# Motor_Driver_2.net
KiCad netlist of a schematic drawn in Altium Designer
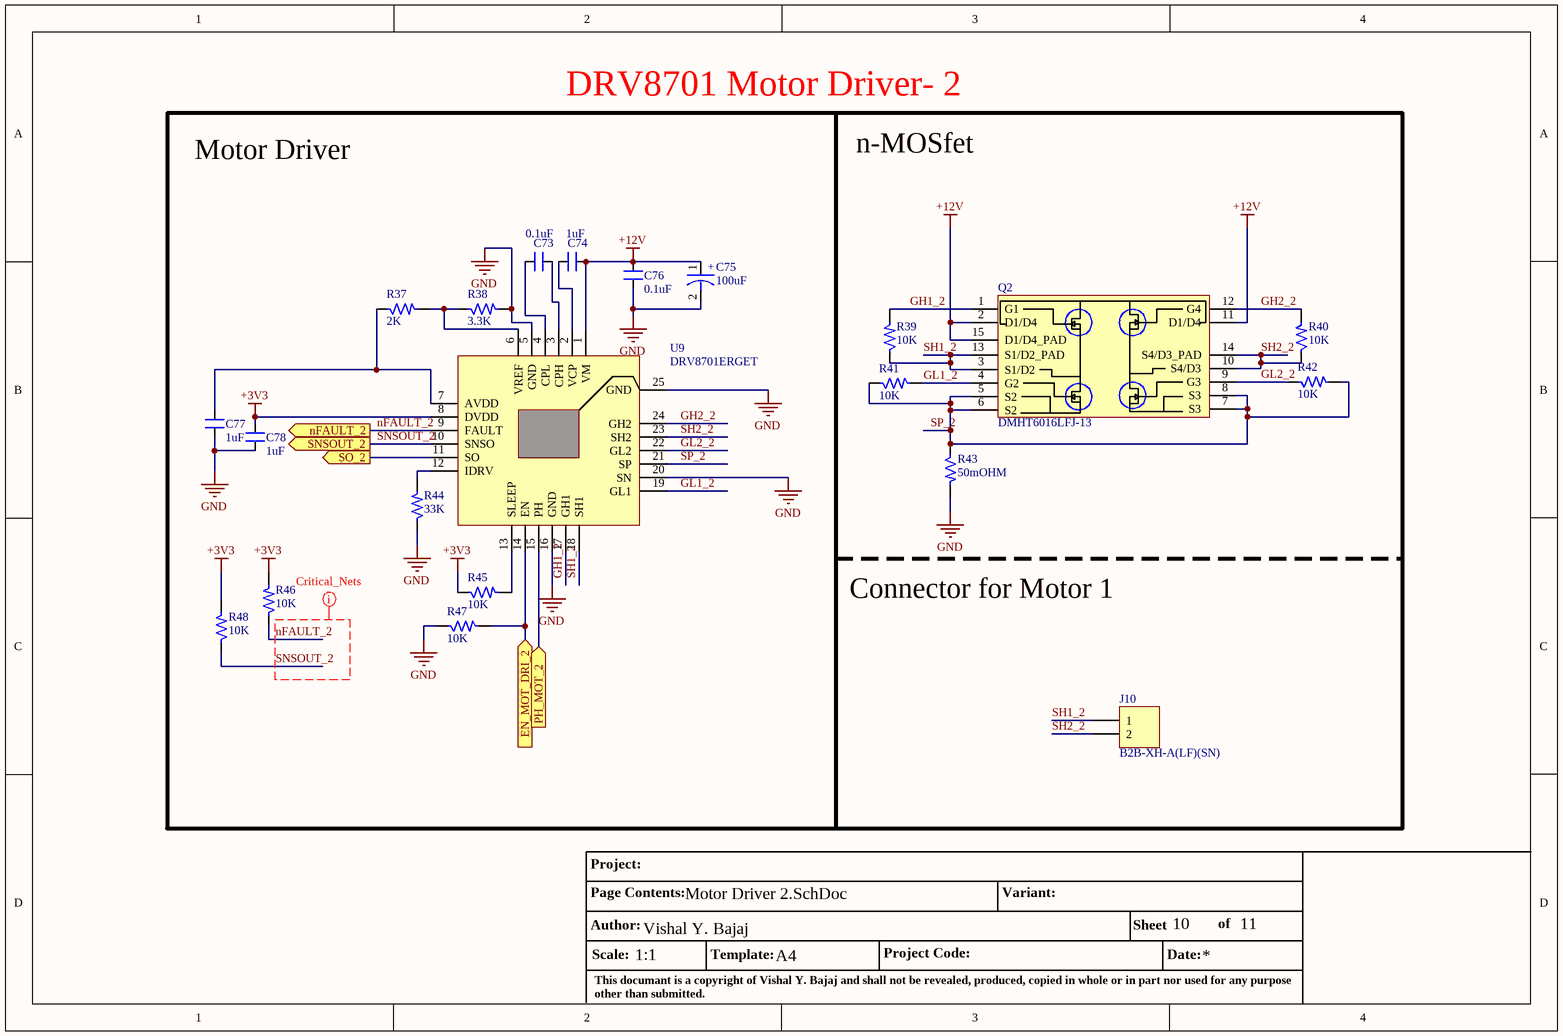
[diagram p0: Motor Driver 2.SchDoc]

(export (version "E")
  (design (tool "Eeschema 10.0.6"))
  (components
    (comp (ref "C73")
      (value "0.1uF")
      (footprint "CAP_0805")
      (description "0.1µF ±10% 50V Ceramic Capacitor X7R 0805 (2012 Metric)")
      (fields
        (field (name "MANUFACTURER") "Samsung")
        (field (name "MANUFACTURER PART NUMBER") "CL21B104KBCNNNC")
      )
      (libsource (lib "ESTEEMPCBLIB") (part "CAP_0.1uF-50V-10%-0805"))
    )
    (comp (ref "C74")
      (value "1uF")
      (footprint "CAP_0805")
      (description "1µF ±5% 50V Ceramic Capacitor X7R 0805 (2012 Metric)")
      (fields
        (field (name "MANUFACTURER") "Samsung")
        (field (name "MANUFACTURER PART NUMBER") "CC0805JKX7R9BB105")
      )
      (libsource (lib "ESTEEMPCBLIB") (part "CAP_1uF-50V-5%-0805"))
    )
    (comp (ref "C75")
      (value "100uF")
      (footprint "ACAP_P236_D305_H303_RAD")
      (description "100µF 25V Aluminum Electrolytic Capacitors Radial, Can - SMD 1000 Hrs @ 105°C")
      (fields
        (field (name "MANUFACTURER") "Nichicon")
        (field (name "MANUFACTURER PART NUMBER") "UWT1E101MCL1GS")
      )
      (libsource (lib "ESTEEMPCBLIB") (part "CAP-P_100uF-25V-20%-RAD"))
    )
    (comp (ref "C76")
      (value "0.1uF")
      (footprint "CAP_0805")
      (description "0.1µF ±10% 50V Ceramic Capacitor X7R 0805 (2012 Metric)")
      (fields
        (field (name "MANUFACTURER") "Samsung")
        (field (name "MANUFACTURER PART NUMBER") "CL21B104KBCNNNC")
      )
      (libsource (lib "ESTEEMPCBLIB") (part "CAP_0.1uF-50V-10%-0805"))
    )
    (comp (ref "C77")
      (value "1uF")
      (footprint "CAP_0805")
      (description "1µF ±5% 50V Ceramic Capacitor X7R 0805 (2012 Metric)")
      (fields
        (field (name "MANUFACTURER") "Samsung")
        (field (name "MANUFACTURER PART NUMBER") "CC0805JKX7R9BB105")
      )
      (libsource (lib "ESTEEMPCBLIB") (part "CAP_1uF-50V-5%-0805"))
    )
    (comp (ref "C78")
      (value "1uF")
      (footprint "CAP_0805")
      (description "1µF ±5% 50V Ceramic Capacitor X7R 0805 (2012 Metric)")
      (fields
        (field (name "MANUFACTURER") "Samsung")
        (field (name "MANUFACTURER PART NUMBER") "CC0805JKX7R9BB105")
      )
      (libsource (lib "ESTEEMPCBLIB") (part "CAP_1uF-50V-5%-0805"))
    )
    (comp (ref "J10")
      (value "B2B-XH-A(LF)(SN)")
      (footprint "CON2_100_B2B-XH-A_TH_ST")
      (description "2 Pins, 1 Row 2.54mm Pitch, Straight Connector, male")
      (fields (field (name "MANUFACTURER") "JST") (field (name "MATING PART NUMBER") "XHP-2"))
      (libsource (lib "ESTEEMPCBLIB") (part "CON-PLG_2X1-100-ST-TH"))
    )
    (comp (ref "Q2")
      (value "DMHT6016LFJ-13")
      (footprint "DFN5045-12_33_212_27X15_SMD_1")
      (description "Mosfet Array 4 N-Channel 14.8A (Ta) Surface Mount V-DFN5045-12")
      (fields (field (name "MANUFACTURER") "ON Semiconductor"))
      (libsource (lib "ESTEEMPCBLIB") (part "MOSFET-N_60V-14.8A-V-DFN5045-12"))
    )
    (comp (ref "R37")
      (value "2K")
      (footprint "RES_0805")
      (description "2 kOhms ±1% 0.125W, 1/8W Chip Resistor 0805 (2012 Metric) Moisture Resistant Thick Film")
      (fields
        (field (name "MANUFACTURER") "TE Connectivity")
        (field (name "MANUFACTURER PART NUMBER") "RC0805FR-072KL")
      )
      (libsource (lib "ESTEEMPCBLIB") (part "RES_2K-0.125W-1%-0805"))
    )
    (comp (ref "R38")
      (value "3.3K")
      (footprint "RES_0805")
      (description "3.3 kOhms ±1% 0.125W, 1/8W Chip Resistor 0805 (2012 Metric) Thick Film")
      (fields (field (name "MANUFACTURER") "Panasonic") (field (name "MANUFACTURER PART NUMBER") "1623214-1"))
      (libsource (lib "ESTEEMPCBLIB") (part "RES_3.3K-0.125W-1%-0805"))
    )
    (comp (ref "R39")
      (value "10K")
      (footprint "RES_0603")
      (description "10 kOhms ±1% 0.1W, 1/10W Chip Resistor 0603 (1608 Metric) Automotive AEC-Q200 Thick Film")
      (fields (field (name "MANUFACTURER") "Walsin") (field (name "MANUFACTURER PART NUMBER") "WR06X1002FTL"))
      (libsource (lib "ESTEEMPCBLIB") (part "RES_10K-0.1W-1%-0603"))
    )
    (comp (ref "R40")
      (value "10K")
      (footprint "RES_0603")
      (description "10 kOhms ±1% 0.1W, 1/10W Chip Resistor 0603 (1608 Metric) Automotive AEC-Q200 Thick Film")
      (fields (field (name "MANUFACTURER") "Walsin") (field (name "MANUFACTURER PART NUMBER") "WR06X1002FTL"))
      (libsource (lib "ESTEEMPCBLIB") (part "RES_10K-0.1W-1%-0603"))
    )
    (comp (ref "R41")
      (value "10K")
      (footprint "RES_0603")
      (description "10 kOhms ±1% 0.1W, 1/10W Chip Resistor 0603 (1608 Metric) Automotive AEC-Q200 Thick Film")
      (fields (field (name "MANUFACTURER") "Walsin") (field (name "MANUFACTURER PART NUMBER") "WR06X1002FTL"))
      (libsource (lib "ESTEEMPCBLIB") (part "RES_10K-0.1W-1%-0603"))
    )
    (comp (ref "R42")
      (value "10K")
      (footprint "RES_0603")
      (description "10 kOhms ±1% 0.1W, 1/10W Chip Resistor 0603 (1608 Metric) Automotive AEC-Q200 Thick Film")
      (fields (field (name "MANUFACTURER") "Walsin") (field (name "MANUFACTURER PART NUMBER") "WR06X1002FTL"))
      (libsource (lib "ESTEEMPCBLIB") (part "RES_10K-0.1W-1%-0603"))
    )
    (comp (ref "R43")
      (value "50mOHM")
      (footprint "RES_2512")
      (fields
        (field (name "MANUFACTURER") "Yageo")
        (field (name "MANUFACTURER PART NUMBER") "PA2512FKF7W0R05E")
      )
      (libsource (lib "ESTEEMPCBLIB") (part "RES_50mOhm-2W-1%-2512"))
    )
    (comp (ref "R44")
      (value "33K")
      (footprint "RES_0805")
      (fields
        (field (name "MANUFACTURER") "Vishay BCcomponents")
        (field (name "MANUFACTURER PART NUMBER") "CRG0805F33K")
      )
      (libsource (lib "ESTEEMPCBLIB") (part "RES_33K-0.125W-1%-0805"))
    )
    (comp (ref "R45")
      (value "10K")
      (footprint "RES_0603")
      (description "10 kOhms ±1% 0.1W, 1/10W Chip Resistor 0603 (1608 Metric) Automotive AEC-Q200 Thick Film")
      (fields (field (name "MANUFACTURER") "Walsin") (field (name "MANUFACTURER PART NUMBER") "WR06X1002FTL"))
      (libsource (lib "ESTEEMPCBLIB") (part "RES_10K-0.1W-1%-0603"))
    )
    (comp (ref "R46")
      (value "10K")
      (footprint "RES_0805")
      (description "10 kOhms ±1% 0.125W, 1/8W Chip Resistor 0805 (2012 Metric) Automotive AEC-Q200 Thick Film")
      (fields (field (name "MANUFACTURER") "CTS") (field (name "MANUFACTURER PART NUMBER") "WR08X1002FTL"))
      (libsource (lib "ESTEEMPCBLIB") (part "RES_10K-0.125W-1%-0805"))
    )
    (comp (ref "R47")
      (value "10K")
      (footprint "RES_0603")
      (description "10 kOhms ±1% 0.1W, 1/10W Chip Resistor 0603 (1608 Metric) Automotive AEC-Q200 Thick Film")
      (fields (field (name "MANUFACTURER") "Walsin") (field (name "MANUFACTURER PART NUMBER") "WR06X1002FTL"))
      (libsource (lib "ESTEEMPCBLIB") (part "RES_10K-0.1W-1%-0603"))
    )
    (comp (ref "R48")
      (value "10K")
      (footprint "RES_0805")
      (description "10 kOhms ±1% 0.125W, 1/8W Chip Resistor 0805 (2012 Metric) Automotive AEC-Q200 Thick Film")
      (fields (field (name "MANUFACTURER") "CTS") (field (name "MANUFACTURER PART NUMBER") "WR08X1002FTL"))
      (libsource (lib "ESTEEMPCBLIB") (part "RES_10K-0.125W-1%-0805"))
    )
    (comp (ref "U9")
      (value "DRV8701ERGET")
      (footprint "VFQFN24_19.6_196_12X32_SMD_1")
      (description "Motor Driver Power MOSFET Parallel 24-VQFN (4x4)")
      (fields (field (name "MANUFACTURER") "Texas Instruments"))
      (libsource (lib "ESTEEMPCBLIB") (part "IC_DRV8701ERGET"))
    )
  )
  (nets
    (net (code "1") (name "+3V3") (class "Default")
      (node (ref "C78") (pin "2") (pinfunction "2_2") (pintype "passive"))
      (node (ref "R45") (pin "1") (pinfunction "1_1") (pintype "passive"))
      (node (ref "R46") (pin "2") (pinfunction "2_2") (pintype "passive"))
      (node (ref "R48") (pin "2") (pinfunction "2_2") (pintype "passive"))
      (node (ref "U9") (pin "8") (pinfunction "DVDD_8") (pintype "passive"))
    )
    (net (code "2") (name "+12V") (class "Default")
      (node (ref "C74") (pin "2") (pinfunction "2_2") (pintype "passive"))
      (node (ref "C75") (pin "1") (pinfunction "1_1") (pintype "passive"))
      (node (ref "C76") (pin "2") (pinfunction "2_2") (pintype "passive"))
      (node (ref "Q2") (pin "11") (pinfunction "D1/D4_11") (pintype "passive"))
      (node (ref "Q2") (pin "15") (pinfunction "D1/D4_PAD_15") (pintype "passive"))
      (node (ref "Q2") (pin "2") (pinfunction "D1/D4_2") (pintype "passive"))
      (node (ref "U9") (pin "1") (pinfunction "VM_1") (pintype "passive"))
    )
    (net (code "3") (name "/EN_MOT_DRI_2") (class "Default")
      (node (ref "R47") (pin "2") (pinfunction "2_2") (pintype "passive"))
      (node (ref "U9") (pin "14") (pinfunction "EN_14") (pintype "passive"))
    )
    (net (code "4") (name "/GH1_2") (class "Default")
      (node (ref "Q2") (pin "1") (pinfunction "G1_1") (pintype "passive"))
      (node (ref "R39") (pin "2") (pinfunction "2_2") (pintype "passive"))
      (node (ref "U9") (pin "17") (pinfunction "GH1_17") (pintype "passive"))
    )
    (net (code "5") (name "/GH2_2") (class "Default")
      (node (ref "Q2") (pin "12") (pinfunction "G4_12") (pintype "passive"))
      (node (ref "R40") (pin "2") (pinfunction "2_2") (pintype "passive"))
      (node (ref "U9") (pin "24") (pinfunction "GH2_24") (pintype "passive"))
    )
    (net (code "6") (name "/GL1_2") (class "Default")
      (node (ref "Q2") (pin "4") (pinfunction "G2_4") (pintype "passive"))
      (node (ref "R41") (pin "2") (pinfunction "2_2") (pintype "passive"))
      (node (ref "U9") (pin "19") (pinfunction "GL1_19") (pintype "passive"))
    )
    (net (code "7") (name "/GL2_2") (class "Default")
      (node (ref "Q2") (pin "9") (pinfunction "G3_9") (pintype "passive"))
      (node (ref "R42") (pin "1") (pinfunction "1_1") (pintype "passive"))
      (node (ref "U9") (pin "22") (pinfunction "GL2_22") (pintype "passive"))
    )
    (net (code "8") (name "/PH_MOT_2") (class "Default")
      (node (ref "U9") (pin "15") (pinfunction "PH_15") (pintype "passive"))
    )
    (net (code "9") (name "/SH1_2") (class "Default")
      (node (ref "J10") (pin "1") (pinfunction "1_1") (pintype "passive"))
      (node (ref "Q2") (pin "13") (pinfunction "S1/D2_PAD_13") (pintype "passive"))
      (node (ref "Q2") (pin "3") (pinfunction "S1/D2_3") (pintype "passive"))
      (node (ref "R39") (pin "1") (pinfunction "1_1") (pintype "passive"))
      (node (ref "U9") (pin "18") (pinfunction "SH1_18") (pintype "passive"))
    )
    (net (code "10") (name "/SH2_2") (class "Default")
      (node (ref "J10") (pin "2") (pinfunction "2_2") (pintype "passive"))
      (node (ref "Q2") (pin "10") (pinfunction "S4/D3_10") (pintype "passive"))
      (node (ref "Q2") (pin "14") (pinfunction "S4/D3_PAD_14") (pintype "passive"))
      (node (ref "R40") (pin "1") (pinfunction "1_1") (pintype "passive"))
      (node (ref "U9") (pin "23") (pinfunction "SH2_23") (pintype "passive"))
    )
    (net (code "11") (name "/SNSOUT_2") (class "Default")
      (node (ref "R48") (pin "1") (pinfunction "1_1") (pintype "passive"))
      (node (ref "U9") (pin "10") (pinfunction "SNSO_10") (pintype "passive"))
    )
    (net (code "12") (name "/SO_2") (class "Default")
      (node (ref "U9") (pin "11") (pinfunction "SO_11") (pintype "passive"))
    )
    (net (code "13") (name "/SP_2") (class "Default")
      (node (ref "Q2") (pin "5") (pinfunction "S2_5") (pintype "passive"))
      (node (ref "Q2") (pin "6") (pinfunction "S2_6") (pintype "passive"))
      (node (ref "Q2") (pin "7") (pinfunction "S3_7") (pintype "passive"))
      (node (ref "Q2") (pin "8") (pinfunction "S3_8") (pintype "passive"))
      (node (ref "R41") (pin "1") (pinfunction "1_1") (pintype "passive"))
      (node (ref "R42") (pin "2") (pinfunction "2_2") (pintype "passive"))
      (node (ref "R43") (pin "1") (pinfunction "1_1") (pintype "passive"))
      (node (ref "U9") (pin "21") (pinfunction "SP_21") (pintype "passive"))
    )
    (net (code "14") (name "/nFAULT_2") (class "Default")
      (node (ref "R46") (pin "1") (pinfunction "1_1") (pintype "passive"))
      (node (ref "U9") (pin "9") (pinfunction "FAULT_9") (pintype "passive"))
    )
    (net (code "15") (name "GND") (class "Default")
      (node (ref "C75") (pin "2") (pinfunction "2_2") (pintype "passive"))
      (node (ref "C76") (pin "1") (pinfunction "1_1") (pintype "passive"))
      (node (ref "C77") (pin "1") (pinfunction "1_1") (pintype "passive"))
      (node (ref "C78") (pin "1") (pinfunction "1_1") (pintype "passive"))
      (node (ref "R38") (pin "2") (pinfunction "2_2") (pintype "passive"))
      (node (ref "R43") (pin "2") (pinfunction "2_2") (pintype "passive"))
      (node (ref "R44") (pin "1") (pinfunction "1_1") (pintype "passive"))
      (node (ref "R47") (pin "1") (pinfunction "1_1") (pintype "passive"))
      (node (ref "U9") (pin "16") (pinfunction "GND_16") (pintype "passive"))
      (node (ref "U9") (pin "20") (pinfunction "SN_20") (pintype "passive"))
      (node (ref "U9") (pin "25") (pinfunction "GND_25") (pintype "passive"))
      (node (ref "U9") (pin "5") (pinfunction "GND_5") (pintype "passive"))
    )
    (net (code "16") (name "Net-(U9-AVDD)") (class "Default")
      (node (ref "C77") (pin "2") (pinfunction "2_2") (pintype "passive"))
      (node (ref "R37") (pin "1") (pinfunction "1_1") (pintype "passive"))
      (node (ref "U9") (pin "7") (pinfunction "AVDD_7") (pintype "passive"))
    )
    (net (code "17") (name "Net-(U9-CPH)") (class "Default")
      (node (ref "C73") (pin "1") (pinfunction "1_1") (pintype "passive"))
      (node (ref "U9") (pin "3") (pinfunction "CPH_3") (pintype "passive"))
    )
    (net (code "18") (name "Net-(U9-CPL)") (class "Default")
      (node (ref "C73") (pin "2") (pinfunction "2_2") (pintype "passive"))
      (node (ref "U9") (pin "4") (pinfunction "CPL_4") (pintype "passive"))
    )
    (net (code "19") (name "Net-(U9-IDRV)") (class "Default")
      (node (ref "R44") (pin "2") (pinfunction "2_2") (pintype "passive"))
      (node (ref "U9") (pin "12") (pinfunction "IDRV_12") (pintype "passive"))
    )
    (net (code "20") (name "Net-(U9-SLEEP)") (class "Default")
      (node (ref "R45") (pin "2") (pinfunction "2_2") (pintype "passive"))
      (node (ref "U9") (pin "13") (pinfunction "SLEEP_13") (pintype "passive"))
    )
    (net (code "21") (name "Net-(U9-VCP)") (class "Default")
      (node (ref "C74") (pin "1") (pinfunction "1_1") (pintype "passive"))
      (node (ref "U9") (pin "2") (pinfunction "VCP_2") (pintype "passive"))
    )
    (net (code "22") (name "Net-(U9-VREF)") (class "Default")
      (node (ref "R37") (pin "2") (pinfunction "2_2") (pintype "passive"))
      (node (ref "R38") (pin "1") (pinfunction "1_1") (pintype "passive"))
      (node (ref "U9") (pin "6") (pinfunction "VREF_6") (pintype "passive"))
    )
  )
)
